# Button_schem.net
KiCad netlist of a schematic drawn in Altium Designer
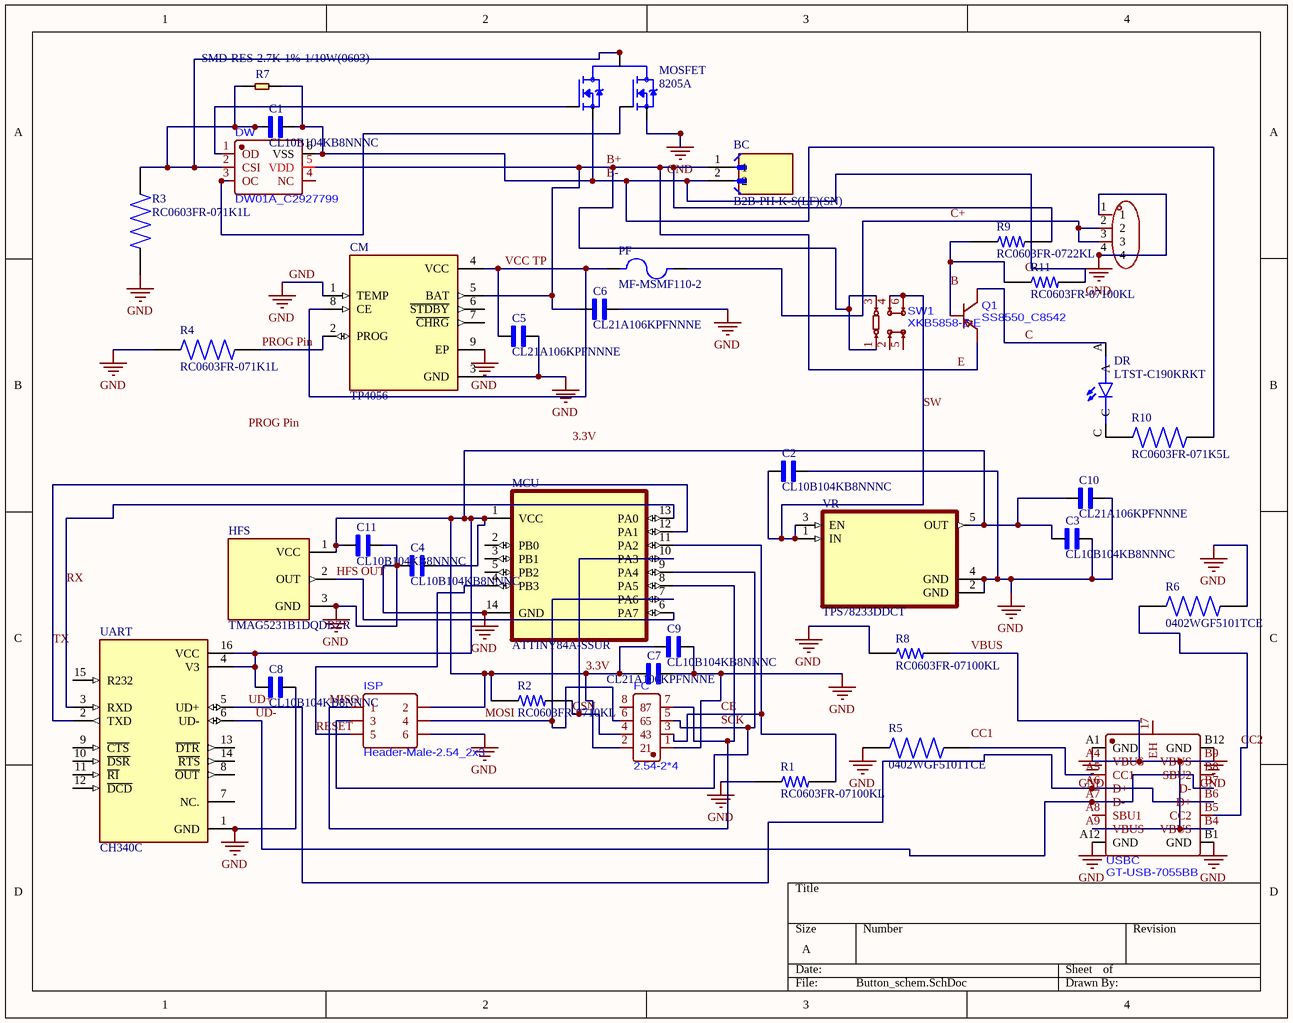
[diagram p0: Button_schem.SchDoc]

(export (version "E")
  (design (tool "Eeschema 10.0.6"))
  (components
    (comp (ref "BC")
      (value "B2B-PH-K-S(LF)(SN)")
      (footprint "JST_B2B-PH-K-S(LF)(SN)")
      (description "Connector Header Through Hole 2 position 0.079 (2.00mm)")
      (fields (field (name "MF") "JST") (field (name "MP") "B2B-PH-K-S (LF)(SN)"))
      (libsource (lib "B2B-PH-K-S_LF__SN_") (part "B2B-PH-K-S(LF)(SN)"))
    )
    (comp (ref "C1")
      (value "CL10B104KB8NNNC")
      (footprint "CAPC1608X90N")
      (description "0.1 ÂµF Â±10% 50V Ceramic Capacitor X7R 0603 (1608 Metric)")
      (fields (field (name "MF") "Samsung Electro-Mechanics"))
      (libsource (lib "CL10B104KB8NNNC") (part "CL10B104KB8NNNC"))
    )
    (comp (ref "C2")
      (value "CL10B104KB8NNNC")
      (footprint "CAPC1608X90N")
      (description "0.1 ÂµF Â±10% 50V Ceramic Capacitor X7R 0603 (1608 Metric)")
      (fields (field (name "MF") "Samsung Electro-Mechanics"))
      (libsource (lib "CL10B104KB8NNNC") (part "CL10B104KB8NNNC"))
    )
    (comp (ref "C3")
      (value "CL10B104KB8NNNC")
      (footprint "CAPC1608X90N")
      (description "0.1 ÂµF Â±10% 50V Ceramic Capacitor X7R 0603 (1608 Metric)")
      (fields (field (name "MF") "Samsung Electro-Mechanics"))
      (libsource (lib "CL10B104KB8NNNC") (part "CL10B104KB8NNNC"))
    )
    (comp (ref "C4")
      (value "CL10B104KB8NNNC")
      (footprint "CAPC1608X90N")
      (description "0.1 ÂµF Â±10% 50V Ceramic Capacitor X7R 0603 (1608 Metric)")
      (fields (field (name "MF") "Samsung Electro-Mechanics"))
      (libsource (lib "CL10B104KB8NNNC") (part "CL10B104KB8NNNC"))
    )
    (comp (ref "C5")
      (value "CL21A106KPFNNNE")
      (footprint "CAPC2012X135N")
      (description "10 ÂµF Â±10% 10V Ceramic Capacitor X5R 0805 (2012 Metric)")
      (fields (field (name "MF") "Samsung"))
      (libsource (lib "CL21A106KPFNNNE") (part "CL21A106KPFNNNE"))
    )
    (comp (ref "C6")
      (value "CL21A106KPFNNNE")
      (footprint "CAPC2012X135N")
      (description "10 ÂµF Â±10% 10V Ceramic Capacitor X5R 0805 (2012 Metric)")
      (fields (field (name "MF") "Samsung"))
      (libsource (lib "CL21A106KPFNNNE") (part "CL21A106KPFNNNE"))
    )
    (comp (ref "C7")
      (value "CL21A106KPFNNNE")
      (footprint "CAPC2012X135N")
      (description "10 ÂµF Â±10% 10V Ceramic Capacitor X5R 0805 (2012 Metric)")
      (fields (field (name "MF") "Samsung"))
      (libsource (lib "CL21A106KPFNNNE") (part "CL21A106KPFNNNE"))
    )
    (comp (ref "C8")
      (value "CL10B104KB8NNNC")
      (footprint "CAPC1608X90N")
      (description "0.1 ÂµF Â±10% 50V Ceramic Capacitor X7R 0603 (1608 Metric)")
      (fields (field (name "MF") "Samsung Electro-Mechanics"))
      (libsource (lib "CL10B104KB8NNNC") (part "CL10B104KB8NNNC"))
    )
    (comp (ref "C9")
      (value "CL10B104KB8NNNC")
      (footprint "CAPC1608X90N")
      (description "0.1 ÂµF Â±10% 50V Ceramic Capacitor X7R 0603 (1608 Metric)")
      (fields (field (name "MF") "Samsung Electro-Mechanics"))
      (libsource (lib "CL10B104KB8NNNC") (part "CL10B104KB8NNNC"))
    )
    (comp (ref "C10")
      (value "CL21A106KPFNNNE")
      (footprint "CAPC2012X135N")
      (description "10 ÂµF Â±10% 10V Ceramic Capacitor X5R 0805 (2012 Metric)")
      (fields (field (name "MF") "Samsung"))
      (libsource (lib "CL21A106KPFNNNE") (part "CL21A106KPFNNNE"))
    )
    (comp (ref "C11")
      (value "CL10B104KB8NNNC")
      (footprint "CAPC1608X90N")
      (description "0.1 ÂµF Â±10% 50V Ceramic Capacitor X7R 0603 (1608 Metric)")
      (fields (field (name "MF") "Samsung Electro-Mechanics"))
      (libsource (lib "CL10B104KB8NNNC") (part "CL10B104KB8NNNC"))
    )
    (comp (ref "CM")
      (value "TP4056")
      (footprint "SOP127P600X175-9N")
      (description "Complete single cell Li-Ion battery with a constant current / constant voltage linear charger")
      (fields (field (name "MF") "NanJing Top Power ASIC Corp."))
      (libsource (lib "TP4056") (part "TP4056"))
    )
    (comp (ref "DR")
      (value "LTST-C190KRKT")
      (footprint "LEDC1608X35N")
      (description "Red 631nm LED Indication - Discrete 2V 0603 (1608 Metric)")
      (fields (field (name "MF") "Lite-On Inc."))
      (libsource (lib "LTST-C190KRKT") (part "LTST-C190KRKT"))
    )
    (comp (ref "DW")
      (value "DW01A_C2927799")
      (footprint "SOT-23-6_L2.9-W1.6-P0.95-LS2.8-BL")
      (libsource (lib "DW01A") (part "DW01A_C2927799"))
    )
    (comp (ref "FC")
      (value "2.54-2*4")
      (footprint "HDR-TH_8P-P2.54-V-F-R2-C4-S2.54")
      (libsource (lib "2.54-Two-Four-FC") (part "2.54-2*4"))
    )
    (comp (ref "HFS")
      (value "TMAG5231B1DQDBZR")
      (footprint "SOT95P237X112-3N")
      (description "Low-power, low-voltage (1.65 V to 5.5 V) Hall-effect switch")
      (fields (field (name "MF") "Texas Instruments"))
      (libsource (lib "TMAG5231B1DQDBZR") (part "TMAG5231B1DQDBZR"))
    )
    (comp (ref "ISP")
      (value "Header-Male-2.54_2x3")
      (footprint "HDR-TH_6P-P2.54-V-M-R2-C3-S2.54-1")
      (libsource (lib "Header-Male-2.54_2x3") (part "Header-Male-2.54_2x3"))
    )
    (comp (ref "MC")
      (value "YZ92015035T-04025-01")
      (footprint "CONN-SMD_4P-P2.50_YZ92015035T-04025-01")
      (libsource (lib "YZ92015035T-04025-01") (part "YZ92015035T-04025-01"))
    )
    (comp (ref "MCU")
      (value "ATTINY84A-SSUR")
      (footprint "SOIC127P600X175-14N")
      (description "AVR AVRÂ® ATtiny Microcontroller IC 8-Bit 20MHz 8KB (4K x 16) FLASH 14-SOIC")
      (fields (field (name "MF") "Microchip Technology"))
      (libsource (lib "ATTINY84A-SSUR") (part "ATTINY84A-SSUR"))
    )
    (comp (ref "MOSFET")
      (value "8205A")
      (footprint "SOT95P285X140-6N")
      (description "Mosfet Array 20V 5A 830mW (Ta) Surface Mount SOT-23-6")
      (fields (field (name "MF") "UMW"))
      (libsource (lib "8205A") (part "8205A"))
    )
    (comp (ref "PF")
      (value "MF-MSMF110-2")
      (footprint "FUSER_MF-MSMF110-2")
      (description "Polymeric PTC Resettable Fuse 6V 1.1 A Ih Surface Mount 1812 (4532 Metric), Concave")
      (fields (field (name "MF") "Bourns"))
      (libsource (lib "MF-MSMF110-2") (part "MF-MSMF110-2"))
    )
    (comp (ref "Q1")
      (value "SS8550_C8542")
      (footprint "SOT-23-3_L2.9-W1.3-P1.90-LS2.4-BR")
      (libsource (lib "SS8550_C8542") (part "SS8550_C8542"))
    )
    (comp (ref "R1")
      (value "RC0603FR-07100KL")
      (footprint "RESC1607X60N")
      (description "100 kOhms Â±1% 0.1W, 1/10W Chip Resistor 0603 (1608 Metric) Moisture Resistant Thick Film")
      (fields (field (name "MF") "Yageo"))
      (libsource (lib "RC0603FR-07100KL") (part "RC0603FR-07100KL"))
    )
    (comp (ref "R2")
      (value "RC0603FR-0710KL")
      (footprint "RESC1607X60N")
      (description "10 kOhms Â±1% 0.1W, 1/10W Chip Resistor 0603 (1608 Metric) Moisture Resistant Thick Film")
      (fields (field (name "MF") "Yageo"))
      (libsource (lib "RC0603FR-0710KL") (part "RC0603FR-0710KL"))
    )
    (comp (ref "R3")
      (value "RC0603FR-071K1L")
      (footprint "RESC1608X55N")
      (description "1.1 kOhms Â±1% 0.1W, 1/10W Chip Resistor 0603 (1608 Metric) Moisture Resistant Thick Film")
      (fields (field (name "MF") "Yageo"))
      (libsource (lib "RC0603FR-071K1L") (part "RC0603FR-071K1L"))
    )
    (comp (ref "R4")
      (value "RC0603FR-071K1L")
      (footprint "RESC1608X55N")
      (description "1.1 kOhms Â±1% 0.1W, 1/10W Chip Resistor 0603 (1608 Metric) Moisture Resistant Thick Film")
      (fields (field (name "MF") "Yageo"))
      (libsource (lib "RC0603FR-071K1L") (part "RC0603FR-071K1L"))
    )
    (comp (ref "R5")
      (value "0402WGF5101TCE")
      (footprint "RESC1005X40N")
      (description "5.1K Ohm 1/16W Thick Film Resistor 0402 Chip - Surface Mount")
      (fields (field (name "MF") "Uni-Royal"))
      (libsource (lib "0402WGF5101TCE") (part "0402WGF5101TCE"))
    )
    (comp (ref "R6")
      (value "0402WGF5101TCE")
      (footprint "RESC1005X40N")
      (description "5.1K Ohm 1/16W Thick Film Resistor 0402 Chip - Surface Mount")
      (fields (field (name "MF") "Uni-Royal"))
      (libsource (lib "0402WGF5101TCE") (part "0402WGF5101TCE"))
    )
    (comp (ref "R7")
      (value "SMD-RES-2.7K-1%-1/10W(0603)")
      (footprint "R0603")
      (description "2.7 kOhms Â±1% 0.1W, 1/10W Chip Resistor 0603 (1608 Metric) Moisture Resistant Thick Film")
      (fields (field (name "MF") "Yageo") (field (name "MP") "RC0603FR-072K7L"))
      (libsource (lib "SMD-RES-2.7K-1_-1_10W_0603_") (part "SMD-RES-2.7K-1%-1/10W(0603)"))
    )
    (comp (ref "R8")
      (value "RC0603FR-07100KL")
      (footprint "RESC1607X60N")
      (description "100 kOhms Â±1% 0.1W, 1/10W Chip Resistor 0603 (1608 Metric) Moisture Resistant Thick Film")
      (fields (field (name "MF") "Yageo"))
      (libsource (lib "RC0603FR-07100KL") (part "RC0603FR-07100KL"))
    )
    (comp (ref "R9")
      (value "RC0603FR-0722KL")
      (footprint "RESC1607X60N")
      (description "22 kOhms Â±1% 0.1W, 1/10W Chip Resistor 0603 (1608 Metric) Moisture Resistant Thick Film")
      (fields (field (name "MF") "Yageo"))
      (libsource (lib "RC0603FR-0722KL") (part "RC0603FR-0722KL"))
    )
    (comp (ref "R10")
      (value "RC0603FR-071K5L")
      (footprint "RESC1607X60N")
      (description "1.5 kOhms Â±1% 0.1W, 1/10W Chip Resistor 0603 (1608 Metric) Moisture Resistant Thick Film")
      (fields (field (name "MF") "Yageo"))
      (libsource (lib "RC0603FR-071K5L") (part "RC0603FR-071K5L"))
    )
    (comp (ref "R11")
      (value "RC0603FR-07100KL")
      (footprint "RESC1607X60N")
      (description "100 kOhms Â±1% 0.1W, 1/10W Chip Resistor 0603 (1608 Metric) Moisture Resistant Thick Film")
      (fields (field (name "MF") "Yageo"))
      (libsource (lib "RC0603FR-07100KL") (part "RC0603FR-07100KL"))
    )
    (comp (ref "SW1")
      (value "XKB5858-Z-E")
      (footprint "SW-TH_XKB5858-Z-E")
      (libsource (lib "XKB5858-Z-E") (part "XKB5858-Z-E"))
    )
    (comp (ref "UART")
      (value "CH340C")
      (footprint "SOIC127P600X180-16N")
      (description "USB to serial chip CH340")
      (fields (field (name "MF") "WCH"))
      (libsource (lib "CH340C") (part "CH340C"))
    )
    (comp (ref "USBC")
      (value "GT-USB-7055BB")
      (footprint "USB-C-TH_GT-USB-7055BB")
      (libsource (lib "GT-USB-7055BB") (part "GT-USB-7055BB"))
    )
    (comp (ref "VR")
      (value "TPS78233DDCT")
      (footprint "SOT95P280X110-5N")
      (description "150-mA, nano-IQ, low-dropout voltage regulator with enable from -40Â°C to +125Â°C")
      (fields (field (name "MF") "Texas Instruments"))
      (libsource (lib "TPS78233DDCT") (part "TPS78233DDCT"))
    )
  )
  (nets
    (net (code "1") (name "/3.3V") (class "Default")
      (node (ref "C10") (pin "1") (pinfunction "1_1") (pintype "passive"))
      (node (ref "C11") (pin "1") (pinfunction "1_1") (pintype "passive"))
      (node (ref "C3") (pin "1") (pinfunction "1_1") (pintype "passive"))
      (node (ref "C4") (pin "2") (pinfunction "2_2") (pintype "passive"))
      (node (ref "C7") (pin "1") (pinfunction "1_1") (pintype "passive"))
      (node (ref "C8") (pin "1") (pinfunction "1_1") (pintype "passive"))
      (node (ref "C9") (pin "1") (pinfunction "1_1") (pintype "passive"))
      (node (ref "FC") (pin "2") (pinfunction "2_2") (pintype "passive"))
      (node (ref "HFS") (pin "1") (pinfunction "VCC_1") (pintype "power_in"))
      (node (ref "ISP") (pin "2") (pinfunction "2_2") (pintype "passive"))
      (node (ref "MCU") (pin "1") (pinfunction "VCC_1") (pintype "power_in"))
      (node (ref "R2") (pin "1") (pinfunction "1_1") (pintype "passive"))
      (node (ref "UART") (pin "16") (pinfunction "VCC_16") (pintype "power_in"))
      (node (ref "UART") (pin "4") (pinfunction "V3_4") (pintype "power_in"))
      (node (ref "VR") (pin "5") (pinfunction "OUT_5") (pintype "output"))
    )
    (net (code "3") (name "/B") (class "Default")
      (node (ref "Q1") (pin "1") (pinfunction "B_1") (pintype "passive"))
      (node (ref "R11") (pin "1") (pinfunction "1_1") (pintype "passive"))
      (node (ref "R9") (pin "1") (pinfunction "1_1") (pintype "passive"))
    )
    (net (code "4") (name "/B+") (class "Default")
      (node (ref "BC") (pin "1") (pinfunction "1_1") (pintype "passive"))
      (node (ref "C6") (pin "1") (pinfunction "1_1") (pintype "passive"))
      (node (ref "CM") (pin "5") (pinfunction "BAT_5") (pintype "output"))
      (node (ref "DW") (pin "5") (pinfunction "VDD_5") (pintype "passive"))
      (node (ref "Q1") (pin "2") (pinfunction "E_2") (pintype "passive"))
      (node (ref "R9") (pin "2") (pinfunction "2_2") (pintype "passive"))
      (node (ref "SW1") (pin "1") (pinfunction "1_1") (pintype "passive"))
      (node (ref "SW1") (pin "3") (pinfunction "3_3") (pintype "passive"))
    )
    (net (code "5") (name "/B-") (class "Default")
      (node (ref "BC") (pin "2") (pinfunction "2_2") (pintype "passive"))
      (node (ref "C1") (pin "2") (pinfunction "2_2") (pintype "passive"))
      (node (ref "DW") (pin "6") (pinfunction "VSS_6") (pintype "passive"))
      (node (ref "MOSFET") (pin "1") (pinfunction "S1_1") (pintype "passive"))
      (node (ref "R10") (pin "2") (pinfunction "2_2") (pintype "passive"))
      (node (ref "R11") (pin "2") (pinfunction "2_2") (pintype "passive"))
      (node (ref "R7") (pin "2") (pinfunction "2_2") (pintype "passive"))
    )
    (net (code "6") (name "/C") (class "Default")
      (node (ref "DR") (pin "A") (pinfunction "A_A") (pintype "passive"))
      (node (ref "Q1") (pin "3") (pinfunction "C_3") (pintype "passive"))
    )
    (net (code "7") (name "/C+") (class "Default")
      (node (ref "MC") (pin "2") (pinfunction "2_2") (pintype "passive"))
      (node (ref "MC") (pin "3") (pinfunction "3_3") (pintype "passive"))
      (node (ref "PF") (pin "2") (pinfunction "2_2") (pintype "passive"))
    )
    (net (code "10") (name "/CC2") (class "Default")
      (node (ref "R6") (pin "1") (pinfunction "1_1") (pintype "passive"))
      (node (ref "USBC") (pin "B5") (pinfunction "CC2_B5") (pintype "passive"))
    )
    (net (code "11") (name "/CE") (class "Default")
      (node (ref "FC") (pin "3") (pinfunction "3_3") (pintype "passive"))
      (node (ref "MCU") (pin "11") (pinfunction "PA2_11") (pintype "bidirectional"))
      (node (ref "R1") (pin "2") (pinfunction "2_2") (pintype "passive"))
    )
    (net (code "12") (name "/CSN") (class "Default")
      (node (ref "FC") (pin "4") (pinfunction "4_4") (pintype "passive"))
      (node (ref "MCU") (pin "10") (pinfunction "PA3_10") (pintype "bidirectional"))
      (node (ref "R2") (pin "2") (pinfunction "2_2") (pintype "passive"))
    )
    (net (code "13") (name "/HFS OUT") (class "Default")
      (node (ref "HFS") (pin "2") (pinfunction "OUT_2") (pintype "output"))
      (node (ref "MCU") (pin "6") (pinfunction "PA7_6") (pintype "bidirectional"))
    )
    (net (code "14") (name "/MISO") (class "Default")
      (node (ref "FC") (pin "7") (pinfunction "7_7") (pintype "passive"))
      (node (ref "ISP") (pin "1") (pinfunction "1_1") (pintype "passive"))
      (node (ref "MCU") (pin "8") (pinfunction "PA5_8") (pintype "bidirectional"))
    )
    (net (code "15") (name "/MOSI") (class "Default")
      (node (ref "FC") (pin "6") (pinfunction "6_6") (pintype "passive"))
      (node (ref "ISP") (pin "4") (pinfunction "4_4") (pintype "passive"))
      (node (ref "MCU") (pin "7") (pinfunction "PA6_7") (pintype "bidirectional"))
    )
    (net (code "16") (name "/PROG Pin") (class "Default")
      (node (ref "CM") (pin "2") (pinfunction "PROG_2") (pintype "bidirectional"))
      (node (ref "R4") (pin "2") (pinfunction "2_2") (pintype "passive"))
    )
    (net (code "17") (name "/RESET") (class "Default")
      (node (ref "ISP") (pin "5") (pinfunction "5_5") (pintype "passive"))
      (node (ref "MCU") (pin "4") (pinfunction "PB3_4") (pintype "bidirectional"))
    )
    (net (code "18") (name "/RX") (class "Default")
      (node (ref "MCU") (pin "13") (pinfunction "PA0_13") (pintype "bidirectional"))
      (node (ref "UART") (pin "3") (pinfunction "RXD_3") (pintype "input"))
    )
    (net (code "19") (name "/SCK") (class "Default")
      (node (ref "FC") (pin "5") (pinfunction "5_5") (pintype "passive"))
      (node (ref "ISP") (pin "3") (pinfunction "3_3") (pintype "passive"))
      (node (ref "MCU") (pin "9") (pinfunction "PA4_9") (pintype "bidirectional"))
    )
    (net (code "20") (name "/SW") (class "Default")
      (node (ref "C2") (pin "1") (pinfunction "1_1") (pintype "passive"))
      (node (ref "SW1") (pin "4") (pinfunction "4_4") (pintype "passive"))
      (node (ref "SW1") (pin "6") (pinfunction "6_6") (pintype "passive"))
      (node (ref "VR") (pin "1") (pinfunction "IN_1") (pintype "input"))
      (node (ref "VR") (pin "3") (pinfunction "EN_3") (pintype "input"))
    )
    (net (code "21") (name "/TX") (class "Default")
      (node (ref "MCU") (pin "12") (pinfunction "PA1_12") (pintype "bidirectional"))
      (node (ref "UART") (pin "2") (pinfunction "TXD_2") (pintype "output"))
    )
    (net (code "22") (name "/UD+") (class "Default")
      (node (ref "UART") (pin "5") (pinfunction "UD+_5") (pintype "bidirectional"))
      (node (ref "USBC") (pin "A6") (pinfunction "D+_A6") (pintype "passive"))
      (node (ref "USBC") (pin "B6") (pinfunction "D+_B6") (pintype "passive"))
    )
    (net (code "23") (name "/UD-") (class "Default")
      (node (ref "UART") (pin "6") (pinfunction "UD-_6") (pintype "bidirectional"))
      (node (ref "USBC") (pin "A7") (pinfunction "D-_A7") (pintype "passive"))
      (node (ref "USBC") (pin "B7") (pinfunction "D-_B7") (pintype "passive"))
    )
    (net (code "24") (name "/VBUS") (class "Default")
      (node (ref "R8") (pin "2") (pinfunction "2_2") (pintype "passive"))
      (node (ref "USBC") (pin "A4") (pinfunction "VBUS_A4") (pintype "passive"))
      (node (ref "USBC") (pin "A9") (pinfunction "VBUS_A9") (pintype "passive"))
      (node (ref "USBC") (pin "B4") (pinfunction "VBUS_B4") (pintype "passive"))
      (node (ref "USBC") (pin "B9") (pinfunction "VBUS_B9") (pintype "passive"))
    )
    (net (code "25") (name "/VCC TP") (class "Default")
      (node (ref "C5") (pin "1") (pinfunction "1_1") (pintype "passive"))
      (node (ref "CM") (pin "4") (pinfunction "VCC_4") (pintype "power_in"))
      (node (ref "CM") (pin "8") (pinfunction "CE_8") (pintype "input"))
      (node (ref "PF") (pin "1") (pinfunction "1_1") (pintype "passive"))
    )
    (net (code "26") (name "GND") (class "Default")
      (node (ref "C10") (pin "2") (pinfunction "2_2") (pintype "passive"))
      (node (ref "C11") (pin "2") (pinfunction "2_2") (pintype "passive"))
      (node (ref "C2") (pin "2") (pinfunction "2_2") (pintype "passive"))
      (node (ref "C3") (pin "2") (pinfunction "2_2") (pintype "passive"))
      (node (ref "C4") (pin "1") (pinfunction "1_1") (pintype "passive"))
      (node (ref "C5") (pin "2") (pinfunction "2_2") (pintype "passive"))
      (node (ref "C6") (pin "2") (pinfunction "2_2") (pintype "passive"))
      (node (ref "C7") (pin "2") (pinfunction "2_2") (pintype "passive"))
      (node (ref "C8") (pin "2") (pinfunction "2_2") (pintype "passive"))
      (node (ref "C9") (pin "2") (pinfunction "2_2") (pintype "passive"))
      (node (ref "CM") (pin "1") (pinfunction "TEMP_1") (pintype "input"))
      (node (ref "CM") (pin "3") (pinfunction "GND_3") (pintype "power_in"))
      (node (ref "CM") (pin "9") (pinfunction "EP_9") (pintype "passive"))
      (node (ref "FC") (pin "1") (pinfunction "1_1") (pintype "passive"))
      (node (ref "HFS") (pin "3") (pinfunction "GND_3") (pintype "power_in"))
      (node (ref "ISP") (pin "6") (pinfunction "6_6") (pintype "passive"))
      (node (ref "MC") (pin "1") (pinfunction "1_1") (pintype "passive"))
      (node (ref "MC") (pin "4") (pinfunction "4_4") (pintype "passive"))
      (node (ref "MCU") (pin "14") (pinfunction "GND_14") (pintype "passive"))
      (node (ref "MOSFET") (pin "3") (pinfunction "S2_3") (pintype "passive"))
      (node (ref "R1") (pin "1") (pinfunction "1_1") (pintype "passive"))
      (node (ref "R3") (pin "1") (pinfunction "1_1") (pintype "passive"))
      (node (ref "R4") (pin "1") (pinfunction "1_1") (pintype "passive"))
      (node (ref "R5") (pin "1") (pinfunction "1_1") (pintype "passive"))
      (node (ref "R6") (pin "2") (pinfunction "2_2") (pintype "passive"))
      (node (ref "R8") (pin "1") (pinfunction "1_1") (pintype "passive"))
      (node (ref "UART") (pin "1") (pinfunction "GND_1") (pintype "power_in"))
      (node (ref "USBC") (pin "A1") (pinfunction "GND_A1") (pintype "passive"))
      (node (ref "USBC") (pin "A12") (pinfunction "GND_A12") (pintype "passive"))
      (node (ref "USBC") (pin "B1") (pinfunction "GND_B1") (pintype "passive"))
      (node (ref "USBC") (pin "B12") (pinfunction "GND_B12") (pintype "passive"))
      (node (ref "VR") (pin "2") (pinfunction "GND_2") (pintype "power_in"))
      (node (ref "VR") (pin "4") (pinfunction "GND_4") (pintype "power_in"))
    )
    (net (code "27") (name "Net-(DR-PadC)") (class "Default")
      (node (ref "DR") (pin "C") (pinfunction "C_C") (pintype "passive"))
      (node (ref "R10") (pin "1") (pinfunction "1_1") (pintype "passive"))
    )
    (net (code "28") (name "Net-(DW-CSI)") (class "Default")
      (node (ref "C1") (pin "1") (pinfunction "1_1") (pintype "passive"))
      (node (ref "DW") (pin "2") (pinfunction "CSI_2") (pintype "passive"))
      (node (ref "MOSFET") (pin "2") (pinfunction "D1_D2_2") (pintype "passive"))
      (node (ref "MOSFET") (pin "5") (pinfunction "D1_D2_5") (pintype "passive"))
      (node (ref "R3") (pin "2") (pinfunction "2_2") (pintype "passive"))
      (node (ref "R7") (pin "1") (pinfunction "1_1") (pintype "passive"))
    )
    (net (code "29") (name "Net-(DW-OC)") (class "Default")
      (node (ref "DW") (pin "3") (pinfunction "OC_3") (pintype "passive"))
      (node (ref "MOSFET") (pin "4") (pinfunction "G2_4") (pintype "passive"))
    )
    (net (code "30") (name "Net-(DW-OD)") (class "Default")
      (node (ref "DW") (pin "1") (pinfunction "OD_1") (pintype "passive"))
      (node (ref "MOSFET") (pin "6") (pinfunction "G1_6") (pintype "passive"))
    )
    (net (code "31") (name "Net-(USBC-CC1)") (class "Default")
      (node (ref "R5") (pin "2") (pinfunction "2_2") (pintype "passive"))
      (node (ref "USBC") (pin "A5") (pinfunction "CC1_A5") (pintype "passive"))
    )
    (net (code "32") (name "unconnected-(CM-~{CHRG}-Pad7)") (class "Default")
      (node (ref "CM") (pin "7") (pinfunction "~{CHRG}_7") (pintype "output"))
    )
    (net (code "33") (name "unconnected-(CM-~{STDBY}-Pad6)") (class "Default")
      (node (ref "CM") (pin "6") (pinfunction "~{STDBY}_6") (pintype "output"))
    )
    (net (code "34") (name "unconnected-(DW-NC-Pad4)") (class "Default")
      (node (ref "DW") (pin "4") (pinfunction "NC_4") (pintype "passive"))
    )
    (net (code "35") (name "unconnected-(FC-Pad8)") (class "Default")
      (node (ref "FC") (pin "8") (pinfunction "8_8") (pintype "passive"))
    )
    (net (code "36") (name "unconnected-(MCU-PB0-Pad2)") (class "Default")
      (node (ref "MCU") (pin "2") (pinfunction "PB0_2") (pintype "bidirectional"))
    )
    (net (code "37") (name "unconnected-(MCU-PB1-Pad3)") (class "Default")
      (node (ref "MCU") (pin "3") (pinfunction "PB1_3") (pintype "bidirectional"))
    )
    (net (code "38") (name "unconnected-(MCU-PB2-Pad5)") (class "Default")
      (node (ref "MCU") (pin "5") (pinfunction "PB2_5") (pintype "bidirectional"))
    )
    (net (code "39") (name "unconnected-(SW1-Pad2)") (class "Default")
      (node (ref "SW1") (pin "2") (pinfunction "2_2") (pintype "passive"))
    )
    (net (code "40") (name "unconnected-(SW1-Pad5)") (class "Default")
      (node (ref "SW1") (pin "5") (pinfunction "5_5") (pintype "passive"))
    )
    (net (code "41") (name "unconnected-(UART-NC.-Pad7)") (class "Default")
      (node (ref "UART") (pin "7") (pinfunction "NC._7") (pintype "passive"))
    )
    (net (code "42") (name "unconnected-(UART-R232-Pad15)") (class "Default")
      (node (ref "UART") (pin "15") (pinfunction "R232_15") (pintype "input"))
    )
    (net (code "43") (name "unconnected-(UART-~{CTS}-Pad9)") (class "Default")
      (node (ref "UART") (pin "9") (pinfunction "~{CTS}_9") (pintype "input"))
    )
    (net (code "44") (name "unconnected-(UART-~{DCD}-Pad12)") (class "Default")
      (node (ref "UART") (pin "12") (pinfunction "~{DCD}_12") (pintype "input"))
    )
    (net (code "45") (name "unconnected-(UART-~{DSR}-Pad10)") (class "Default")
      (node (ref "UART") (pin "10") (pinfunction "~{DSR}_10") (pintype "input"))
    )
    (net (code "46") (name "unconnected-(UART-~{DTR}-Pad13)") (class "Default")
      (node (ref "UART") (pin "13") (pinfunction "~{DTR}_13") (pintype "output"))
    )
    (net (code "47") (name "unconnected-(UART-~{OUT}-Pad8)") (class "Default")
      (node (ref "UART") (pin "8") (pinfunction "~{OUT}_8") (pintype "output"))
    )
    (net (code "48") (name "unconnected-(UART-~{RI}-Pad11)") (class "Default")
      (node (ref "UART") (pin "11") (pinfunction "~{RI}_11") (pintype "input"))
    )
    (net (code "49") (name "unconnected-(UART-~{RTS}-Pad14)") (class "Default")
      (node (ref "UART") (pin "14") (pinfunction "~{RTS}_14") (pintype "output"))
    )
    (net (code "50") (name "unconnected-(USBC-EH-Pad17)") (class "Default")
      (node (ref "USBC") (pin "17") (pinfunction "EH_17") (pintype "passive"))
    )
    (net (code "51") (name "unconnected-(USBC-SBU1-PadA8)") (class "Default")
      (node (ref "USBC") (pin "A8") (pinfunction "SBU1_A8") (pintype "passive"))
    )
    (net (code "52") (name "unconnected-(USBC-SBU2-PadB8)") (class "Default")
      (node (ref "USBC") (pin "B8") (pinfunction "SBU2_B8") (pintype "passive"))
    )
  )
)
